# COMSXXXX_Beacon_Rework.net
KiCad netlist of a schematic drawn in Altium Designer
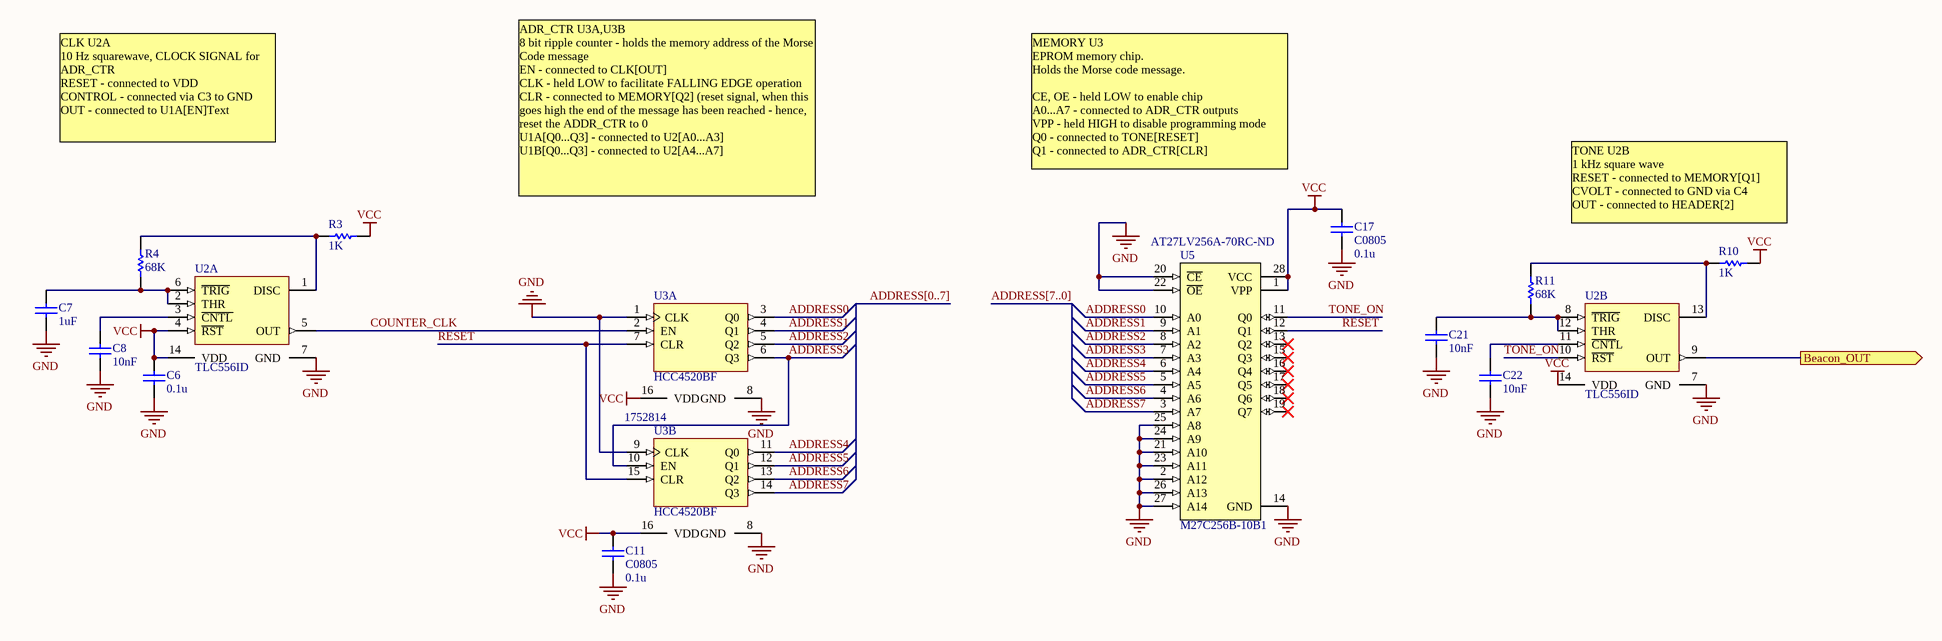
[diagram p0: COMSXXXX_Beacon_Rework.SchDoc]

(export (version "E")
  (design (tool "Eeschema 10.0.6"))
  (components
    (comp (ref "C6")
      (value "0.1u")
      (footprint "CAPC2012M")
      (description "Capacitor")
      (fields (field (name "Comment") "C0805") (field (name "PUBLISHER") "Altium Limited"))
      (libsource (lib "Miscellaneous Devices") (part "Cap"))
    )
    (comp (ref "C7")
      (value "1uF")
      (footprint "CAPC2012M")
      (description "Capacitor")
      (fields (field (name "Comment") "Cap1u") (field (name "PUBLISHER") "Altium Limited"))
      (libsource (lib "Miscellaneous Devices") (part "Cap"))
    )
    (comp (ref "C8")
      (value "10nF")
      (footprint "CAPC2012M")
      (description "Capacitor")
      (fields (field (name "Comment") "Cap") (field (name "PUBLISHER") "Altium Limited"))
      (libsource (lib "Miscellaneous Devices") (part "Cap"))
    )
    (comp (ref "C11")
      (value "C0805")
      (footprint "CAPC2012M")
      (description "Capacitor")
      (fields (field (name "ALTIUM_VALUE") "0.1u") (field (name "PUBLISHER") "Altium Limited"))
      (libsource (lib "Miscellaneous Devices") (part "Cap"))
    )
    (comp (ref "C17")
      (value "C0805")
      (footprint "CAPC2012M")
      (description "Capacitor")
      (fields (field (name "ALTIUM_VALUE") "0.1u") (field (name "PUBLISHER") "Altium Limited"))
      (libsource (lib "Miscellaneous Devices") (part "Cap"))
    )
    (comp (ref "C21")
      (value "10nF")
      (footprint "CAPC2012M")
      (description "Capacitor")
      (fields (field (name "Comment") "Cap") (field (name "PUBLISHER") "Altium Limited"))
      (libsource (lib "Miscellaneous Devices") (part "Cap"))
    )
    (comp (ref "C22")
      (value "10nF")
      (footprint "CAPC2012M")
      (description "Capacitor")
      (fields (field (name "Comment") "Cap") (field (name "PUBLISHER") "Altium Limited"))
      (libsource (lib "Miscellaneous Devices") (part "Cap"))
    )
    (comp (ref "R3")
      (value "1K")
      (footprint "RESC2012M")
      (description "Resistor")
      (fields (field (name "Comment") "Res2") (field (name "PUBLISHER") "Altium Limited"))
      (libsource (lib "Miscellaneous Devices") (part "Res1"))
    )
    (comp (ref "R4")
      (value "68K")
      (footprint "RESC2012M")
      (description "Resistor")
      (fields (field (name "Comment") "Res1") (field (name "PUBLISHER") "Altium Limited"))
      (libsource (lib "Miscellaneous Devices") (part "Res1"))
    )
    (comp (ref "R10")
      (value "1K")
      (footprint "RESC2012M")
      (description "Resistor")
      (fields (field (name "Comment") "Res2") (field (name "PUBLISHER") "Altium Limited"))
      (libsource (lib "Miscellaneous Devices") (part "Res1"))
    )
    (comp (ref "R11")
      (value "68K")
      (footprint "RESC2012M")
      (description "Resistor")
      (fields (field (name "Comment") "Res1") (field (name "PUBLISHER") "Altium Limited"))
      (libsource (lib "Miscellaneous Devices") (part "Res1"))
    )
    (comp (ref "U2")
      (value "TLC556ID")
      (footprint "D014_N")
      (description "Dual LinCMOS Timer")
      (fields (field (name "PUBLISHER") "Altium Limited"))
      (libsource (lib "TI Analog Timer Circuit") (part "TLC556ID"))
    )
    (comp (ref "U3")
      (value "HCC4520BF")
      (footprint "SOIC16_M")
      (description "Dual Binary Up-Counter")
      (fields (field (name "SUPPLIER PART NUMBER 1") "1752814") (field (name "PUBLISHER") "Altium Limited"))
      (libsource (lib "ST Logic Counter") (part "HCC4520BF"))
    )
    (comp (ref "U5")
      (value "M27C256B-10B1")
      (footprint "SOIC127P1199-28AM")
      (description "256 Kbit (32Kb X 8) UV EPROM and OTP EPROM")
      (fields
        (field (name "SUPPLIER PART NUMBER 1") "AT27LV256A-70RC-ND")
        (field (name "PUBLISHER") "Altium Limited")
      )
      (libsource (lib "ST Memory EPROM 16-512 Kbit") (part "M27C256B-10B1"))
    )
  )
  (nets
    (net (code "1") (name "/ADDRESS0") (class "Default")
      (node (ref "U3") (pin "3") (pinfunction "Q0_3") (pintype "output"))
      (node (ref "U5") (pin "10") (pinfunction "A0_10") (pintype "input"))
    )
    (net (code "2") (name "/ADDRESS1") (class "Default")
      (node (ref "U3") (pin "4") (pinfunction "Q1_4") (pintype "output"))
      (node (ref "U5") (pin "9") (pinfunction "A1_9") (pintype "input"))
    )
    (net (code "3") (name "/ADDRESS2") (class "Default")
      (node (ref "U3") (pin "5") (pinfunction "Q2_5") (pintype "output"))
      (node (ref "U5") (pin "8") (pinfunction "A2_8") (pintype "input"))
    )
    (net (code "4") (name "/ADDRESS3") (class "Default")
      (node (ref "U3") (pin "10") (pinfunction "EN_10") (pintype "input"))
      (node (ref "U3") (pin "6") (pinfunction "Q3_6") (pintype "output"))
      (node (ref "U5") (pin "7") (pinfunction "A3_7") (pintype "input"))
    )
    (net (code "5") (name "/ADDRESS4") (class "Default")
      (node (ref "U3") (pin "11") (pinfunction "Q0_11") (pintype "output"))
      (node (ref "U5") (pin "6") (pinfunction "A4_6") (pintype "input"))
    )
    (net (code "6") (name "/ADDRESS5") (class "Default")
      (node (ref "U3") (pin "12") (pinfunction "Q1_12") (pintype "output"))
      (node (ref "U5") (pin "5") (pinfunction "A5_5") (pintype "input"))
    )
    (net (code "7") (name "/ADDRESS6") (class "Default")
      (node (ref "U3") (pin "13") (pinfunction "Q2_13") (pintype "output"))
      (node (ref "U5") (pin "4") (pinfunction "A6_4") (pintype "input"))
    )
    (net (code "8") (name "/ADDRESS7") (class "Default")
      (node (ref "U3") (pin "14") (pinfunction "Q3_14") (pintype "output"))
      (node (ref "U5") (pin "3") (pinfunction "A7_3") (pintype "input"))
    )
    (net (code "11") (name "/Beacon_OUT") (class "Default")
      (node (ref "U2") (pin "9") (pinfunction "OUT_9") (pintype "output"))
    )
    (net (code "12") (name "/COUNTER_CLK") (class "Default")
      (node (ref "U2") (pin "5") (pinfunction "OUT_5") (pintype "output"))
      (node (ref "U3") (pin "2") (pinfunction "EN_2") (pintype "input"))
    )
    (net (code "13") (name "/RESET") (class "Default")
      (node (ref "U3") (pin "15") (pinfunction "CLR_15") (pintype "input"))
      (node (ref "U3") (pin "7") (pinfunction "CLR_7") (pintype "input"))
      (node (ref "U5") (pin "12") (pinfunction "Q1_12") (pintype "bidirectional"))
    )
    (net (code "14") (name "/TONE_ON") (class "Default")
      (node (ref "U2") (pin "10") (pinfunction "~{RST}_10") (pintype "input"))
      (node (ref "U5") (pin "11") (pinfunction "Q0_11") (pintype "bidirectional"))
    )
    (net (code "15") (name "GND") (class "Default")
      (node (ref "C11") (pin "1") (pinfunction "1_1") (pintype "passive"))
      (node (ref "C17") (pin "1") (pinfunction "1_1") (pintype "passive"))
      (node (ref "C21") (pin "2") (pinfunction "2_2") (pintype "passive"))
      (node (ref "C22") (pin "2") (pinfunction "2_2") (pintype "passive"))
      (node (ref "C6") (pin "1") (pinfunction "1_1") (pintype "passive"))
      (node (ref "C7") (pin "2") (pinfunction "2_2") (pintype "passive"))
      (node (ref "C8") (pin "2") (pinfunction "2_2") (pintype "passive"))
      (node (ref "U2") (pin "7") (pinfunction "GND_7") (pintype "power_in"))
      (node (ref "U3") (pin "1") (pinfunction "CLK_1") (pintype "input"))
      (node (ref "U3") (pin "8") (pinfunction "GND_8") (pintype "power_in"))
      (node (ref "U3") (pin "9") (pinfunction "CLK_9") (pintype "input"))
      (node (ref "U5") (pin "14") (pinfunction "GND_14") (pintype "power_in"))
      (node (ref "U5") (pin "2") (pinfunction "A12_2") (pintype "input"))
      (node (ref "U5") (pin "20") (pinfunction "~{CE}_20") (pintype "input"))
      (node (ref "U5") (pin "21") (pinfunction "A10_21") (pintype "input"))
      (node (ref "U5") (pin "22") (pinfunction "~{OE}_22") (pintype "input"))
      (node (ref "U5") (pin "23") (pinfunction "A11_23") (pintype "input"))
      (node (ref "U5") (pin "24") (pinfunction "A9_24") (pintype "input"))
      (node (ref "U5") (pin "25") (pinfunction "A8_25") (pintype "input"))
      (node (ref "U5") (pin "26") (pinfunction "A13_26") (pintype "input"))
      (node (ref "U5") (pin "27") (pinfunction "A14_27") (pintype "input"))
    )
    (net (code "16") (name "Net-(U2A-DISC)") (class "Default")
      (node (ref "R3") (pin "2") (pinfunction "2_2") (pintype "passive"))
      (node (ref "R4") (pin "2") (pinfunction "2_2") (pintype "passive"))
      (node (ref "U2") (pin "1") (pinfunction "DISC_1") (pintype "open_collector"))
    )
    (net (code "17") (name "Net-(U2A-THR)") (class "Default")
      (node (ref "C7") (pin "1") (pinfunction "1_1") (pintype "passive"))
      (node (ref "R4") (pin "1") (pinfunction "1_1") (pintype "passive"))
      (node (ref "U2") (pin "2") (pinfunction "THR_2") (pintype "input"))
      (node (ref "U2") (pin "6") (pinfunction "~{TRIG}_6") (pintype "input"))
    )
    (net (code "18") (name "Net-(U2A-~{CNTL})") (class "Default")
      (node (ref "C8") (pin "1") (pinfunction "1_1") (pintype "passive"))
      (node (ref "U2") (pin "3") (pinfunction "~{CNTL}_3") (pintype "input"))
    )
    (net (code "19") (name "Net-(U2B-DISC)") (class "Default")
      (node (ref "R10") (pin "2") (pinfunction "2_2") (pintype "passive"))
      (node (ref "R11") (pin "1") (pinfunction "1_1") (pintype "passive"))
      (node (ref "U2") (pin "13") (pinfunction "DISC_13") (pintype "open_collector"))
    )
    (net (code "20") (name "Net-(U2B-THR)") (class "Default")
      (node (ref "C21") (pin "1") (pinfunction "1_1") (pintype "passive"))
      (node (ref "R11") (pin "2") (pinfunction "2_2") (pintype "passive"))
      (node (ref "U2") (pin "12") (pinfunction "THR_12") (pintype "input"))
      (node (ref "U2") (pin "8") (pinfunction "~{TRIG}_8") (pintype "input"))
    )
    (net (code "21") (name "Net-(U2B-~{CNT}L)") (class "Default")
      (node (ref "C22") (pin "1") (pinfunction "1_1") (pintype "passive"))
      (node (ref "U2") (pin "11") (pinfunction "~{CNT}L_11") (pintype "input"))
    )
    (net (code "22") (name "VCC") (class "Default")
      (node (ref "C11") (pin "2") (pinfunction "2_2") (pintype "passive"))
      (node (ref "C17") (pin "2") (pinfunction "2_2") (pintype "passive"))
      (node (ref "C6") (pin "2") (pinfunction "2_2") (pintype "passive"))
      (node (ref "R10") (pin "1") (pinfunction "1_1") (pintype "passive"))
      (node (ref "R3") (pin "1") (pinfunction "1_1") (pintype "passive"))
      (node (ref "U2") (pin "14") (pinfunction "VDD_14") (pintype "power_in"))
      (node (ref "U2") (pin "4") (pinfunction "~{RST}_4") (pintype "input"))
      (node (ref "U3") (pin "16") (pinfunction "VDD_16") (pintype "power_in"))
      (node (ref "U5") (pin "1") (pinfunction "VPP_1") (pintype "power_in"))
      (node (ref "U5") (pin "28") (pinfunction "VCC_28") (pintype "power_in"))
    )
    (net (code "23") (name "unconnected-(U5-Q2-Pad13)") (class "Default")
      (node (ref "U5") (pin "13") (pinfunction "Q2_13") (pintype "bidirectional+no_connect"))
    )
    (net (code "24") (name "unconnected-(U5-Q3-Pad15)") (class "Default")
      (node (ref "U5") (pin "15") (pinfunction "Q3_15") (pintype "bidirectional+no_connect"))
    )
    (net (code "25") (name "unconnected-(U5-Q4-Pad16)") (class "Default")
      (node (ref "U5") (pin "16") (pinfunction "Q4_16") (pintype "bidirectional+no_connect"))
    )
    (net (code "26") (name "unconnected-(U5-Q5-Pad17)") (class "Default")
      (node (ref "U5") (pin "17") (pinfunction "Q5_17") (pintype "bidirectional+no_connect"))
    )
    (net (code "27") (name "unconnected-(U5-Q6-Pad18)") (class "Default")
      (node (ref "U5") (pin "18") (pinfunction "Q6_18") (pintype "bidirectional+no_connect"))
    )
    (net (code "28") (name "unconnected-(U5-Q7-Pad19)") (class "Default")
      (node (ref "U5") (pin "19") (pinfunction "Q7_19") (pintype "bidirectional+no_connect"))
    )
  )
)
